# bb_v1.net
KiCad netlist of a schematic drawn in EAGLE
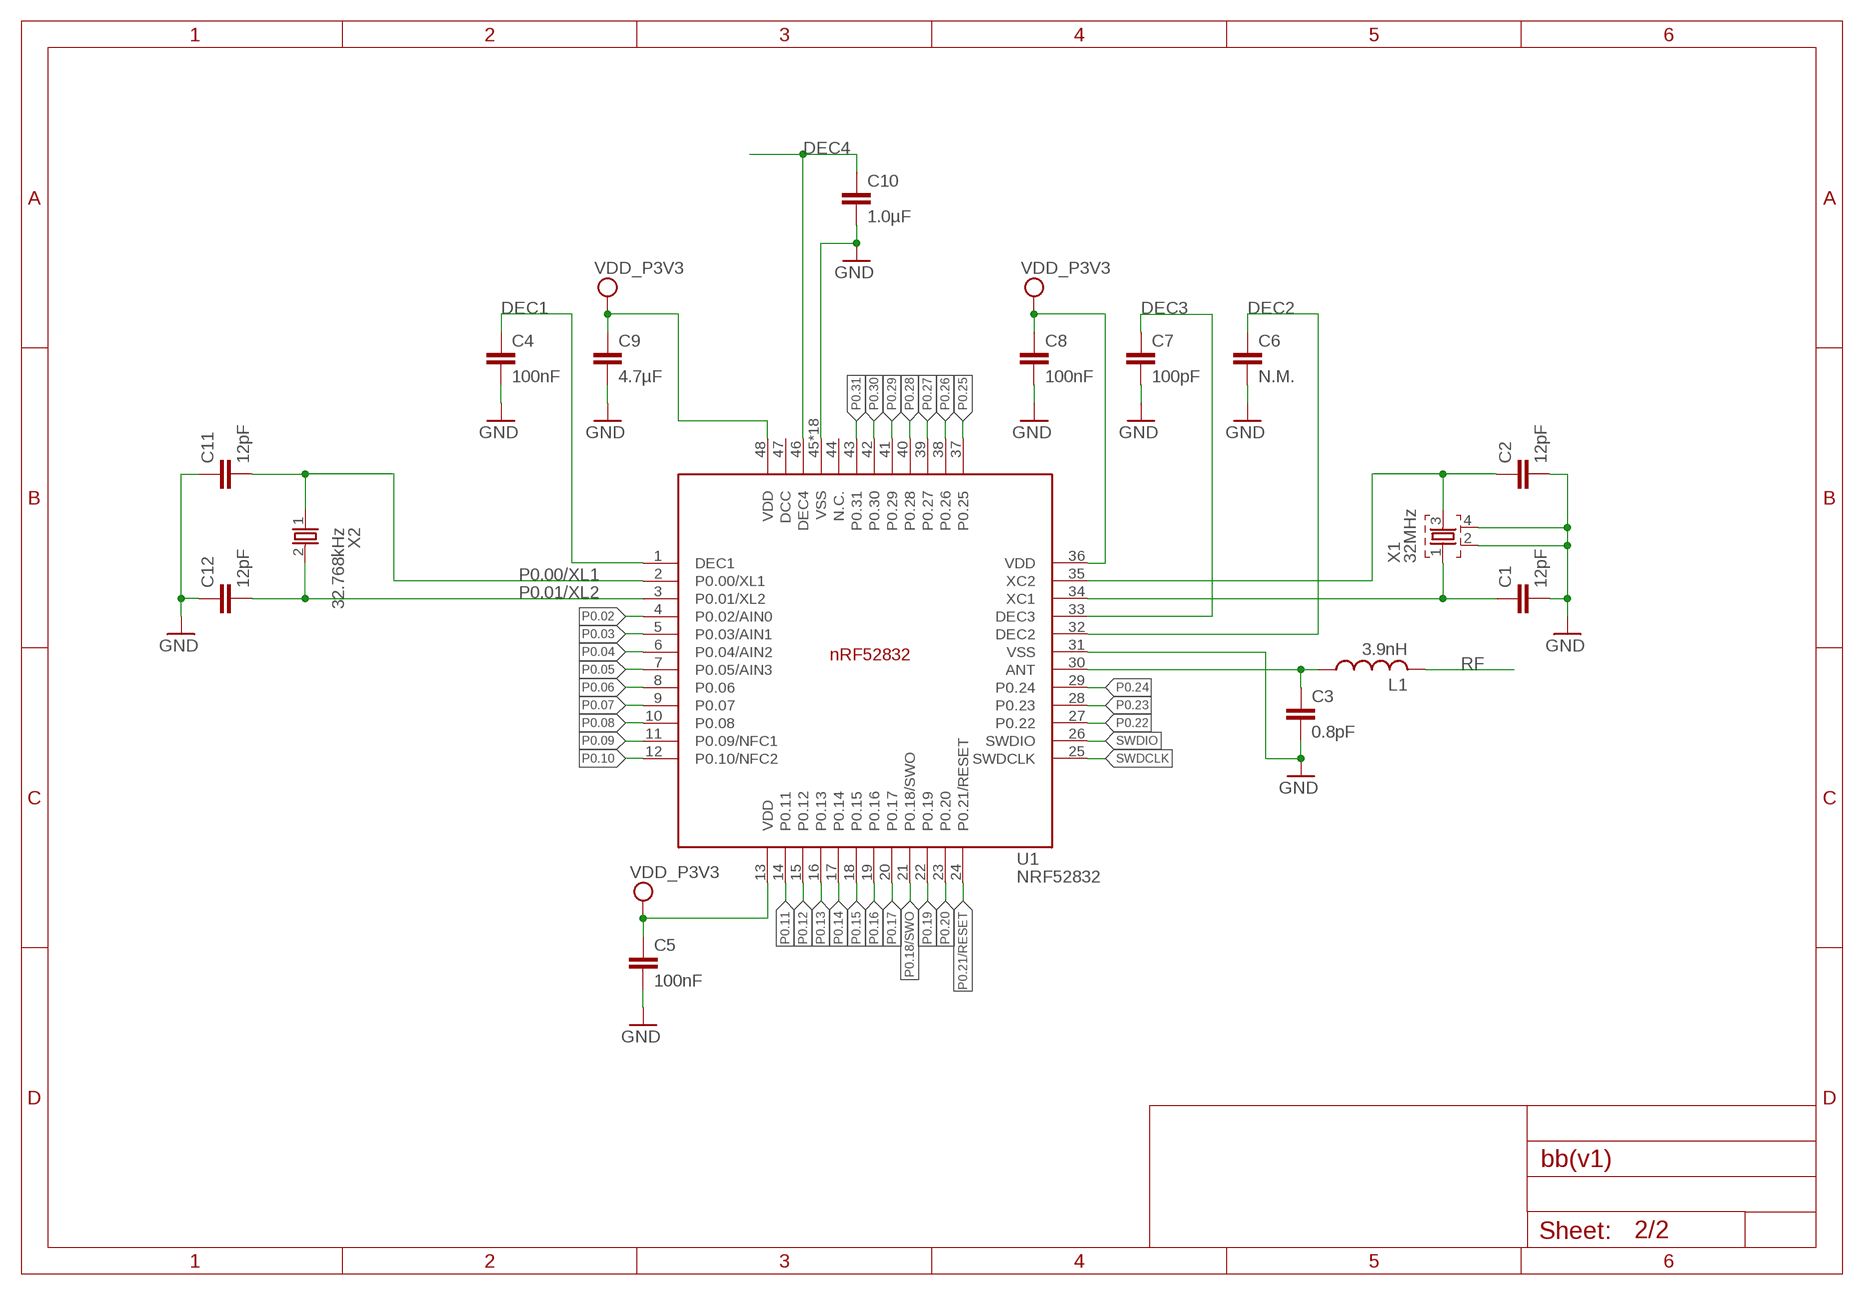
[diagram p0: schematic, sheet 2]

(export (version "E")
  (design (tool "Eeschema 10.0.6"))
  (components
    (comp (ref "C1")
      (value "12pF")
      (footprint "eagle-import:RESC0402_N")
      (libsource (lib "eagle-import") (part "CAPACITOR_0402_N"))
    )
    (comp (ref "C2")
      (value "12pF")
      (footprint "eagle-import:RESC0402_N")
      (libsource (lib "eagle-import") (part "CAPACITOR_0402_N"))
    )
    (comp (ref "C3")
      (value "0.8pF")
      (footprint "eagle-import:RESC0402_N")
      (libsource (lib "eagle-import") (part "CAPACITOR_0402_N"))
    )
    (comp (ref "C4")
      (value "100nF")
      (footprint "eagle-import:RESC0402_N")
      (libsource (lib "eagle-import") (part "CAPACITOR_0402_N"))
    )
    (comp (ref "C5")
      (value "100nF")
      (footprint "eagle-import:RESC0402_N")
      (libsource (lib "eagle-import") (part "CAPACITOR_0402_N"))
    )
    (comp (ref "C6")
      (value "N.M.")
      (footprint "eagle-import:RESC0402_N")
      (libsource (lib "eagle-import") (part "CAPACITOR_0402_N"))
    )
    (comp (ref "C7")
      (value "100pF")
      (footprint "eagle-import:RESC0402_N")
      (libsource (lib "eagle-import") (part "CAPACITOR_0402_N"))
    )
    (comp (ref "C8")
      (value "100nF")
      (footprint "eagle-import:RESC0402_N")
      (libsource (lib "eagle-import") (part "CAPACITOR_0402_N"))
    )
    (comp (ref "C9")
      (value "4.7µF")
      (footprint "eagle-import:RESC0603_N")
      (libsource (lib "eagle-import") (part "CAPACITOR_0603_N"))
    )
    (comp (ref "C10")
      (value "1.0µF")
      (footprint "eagle-import:RESC0603_N")
      (libsource (lib "eagle-import") (part "CAPACITOR_0603_N"))
    )
    (comp (ref "C11")
      (value "12pF")
      (footprint "eagle-import:RESC0402_N")
      (libsource (lib "eagle-import") (part "CAPACITOR_0402_N"))
    )
    (comp (ref "C12")
      (value "12pF")
      (footprint "eagle-import:RESC0402_N")
      (libsource (lib "eagle-import") (part "CAPACITOR_0402_N"))
    )
    (comp (ref "L1")
      (value "3.9nH")
      (footprint "eagle-import:RESC0402_N")
      (libsource (lib "eagle-import") (part "INDUCTOR_0402_N"))
    )
    (comp (ref "U1")
      (value "NRF52832")
      (footprint "eagle-import:QFN40P600X600X90-48_N")
      (libsource (lib "eagle-import") (part "NRF52832"))
    )
    (comp (ref "X1")
      (value "32MHz")
      (footprint "eagle-import:BT-XTAL_2016_N")
      (libsource (lib "eagle-import") (part "XTAL_32MHZ"))
    )
    (comp (ref "X2")
      (value "32.768kHz")
      (footprint "eagle-import:XTAL_3215_N")
      (libsource (lib "eagle-import") (part "XTAL_32KHZ"))
    )
  )
  (nets
    (net (code "1") (name "DEC1") (class "Default")
      (node (ref "C4") (pin "1") (pinfunction "1_1") (pintype "passive"))
      (node (ref "U1") (pin "1") (pinfunction "DEC1_1") (pintype "power_in"))
    )
    (net (code "2") (name "DEC2") (class "Default")
      (node (ref "C6") (pin "1") (pinfunction "1_1") (pintype "passive"))
      (node (ref "U1") (pin "32") (pinfunction "DEC2_32") (pintype "bidirectional"))
    )
    (net (code "3") (name "DEC3") (class "Default")
      (node (ref "C7") (pin "1") (pinfunction "1_1") (pintype "passive"))
      (node (ref "U1") (pin "33") (pinfunction "DEC3_33") (pintype "bidirectional"))
    )
    (net (code "4") (name "DEC4") (class "Default")
      (node (ref "C10") (pin "1") (pinfunction "1_1") (pintype "passive"))
      (node (ref "U1") (pin "46") (pinfunction "DEC4_46") (pintype "power_in"))
    )
    (net (code "5") (name "GND") (class "Default")
      (node (ref "C1") (pin "2") (pinfunction "2_2") (pintype "passive"))
      (node (ref "C10") (pin "2") (pinfunction "2_2") (pintype "passive"))
      (node (ref "C11") (pin "1") (pinfunction "1_1") (pintype "passive"))
      (node (ref "C12") (pin "1") (pinfunction "1_1") (pintype "passive"))
      (node (ref "C2") (pin "2") (pinfunction "2_2") (pintype "passive"))
      (node (ref "C3") (pin "2") (pinfunction "2_2") (pintype "passive"))
      (node (ref "C4") (pin "2") (pinfunction "2_2") (pintype "passive"))
      (node (ref "C5") (pin "2") (pinfunction "2_2") (pintype "passive"))
      (node (ref "C6") (pin "2") (pinfunction "2_2") (pintype "passive"))
      (node (ref "C7") (pin "2") (pinfunction "2_2") (pintype "passive"))
      (node (ref "C8") (pin "2") (pinfunction "2_2") (pintype "passive"))
      (node (ref "C9") (pin "2") (pinfunction "2_2") (pintype "passive"))
      (node (ref "U1") (pin "31") (pinfunction "VSS_31") (pintype "bidirectional"))
      (node (ref "U1") (pin "45") (pinfunction "VSS_45") (pintype "power_in"))
      (node (ref "U1") (pin "PAD") (pinfunction "VSS_PAD") (pintype "power_in"))
      (node (ref "U1") (pin "PAD@VIA01") (pinfunction "VSS_PAD@VIA01") (pintype "power_in"))
      (node (ref "U1") (pin "PAD@VIA02") (pinfunction "VSS_PAD@VIA02") (pintype "power_in"))
      (node (ref "U1") (pin "PAD@VIA03") (pinfunction "VSS_PAD@VIA03") (pintype "power_in"))
      (node (ref "U1") (pin "PAD@VIA04") (pinfunction "VSS_PAD@VIA04") (pintype "power_in"))
      (node (ref "U1") (pin "PAD@VIA05") (pinfunction "VSS_PAD@VIA05") (pintype "power_in"))
      (node (ref "U1") (pin "PAD@VIA06") (pinfunction "VSS_PAD@VIA06") (pintype "power_in"))
      (node (ref "U1") (pin "PAD@VIA07") (pinfunction "VSS_PAD@VIA07") (pintype "power_in"))
      (node (ref "U1") (pin "PAD@VIA08") (pinfunction "VSS_PAD@VIA08") (pintype "power_in"))
      (node (ref "U1") (pin "PAD@VIA09") (pinfunction "VSS_PAD@VIA09") (pintype "power_in"))
      (node (ref "U1") (pin "PAD@VIA10") (pinfunction "VSS_PAD@VIA10") (pintype "power_in"))
      (node (ref "U1") (pin "PAD@VIA11") (pinfunction "VSS_PAD@VIA11") (pintype "power_in"))
      (node (ref "U1") (pin "PAD@VIA12") (pinfunction "VSS_PAD@VIA12") (pintype "power_in"))
      (node (ref "U1") (pin "PAD@VIA13") (pinfunction "VSS_PAD@VIA13") (pintype "power_in"))
      (node (ref "U1") (pin "PAD@VIA14") (pinfunction "VSS_PAD@VIA14") (pintype "power_in"))
      (node (ref "U1") (pin "PAD@VIA15") (pinfunction "VSS_PAD@VIA15") (pintype "power_in"))
      (node (ref "U1") (pin "PAD@VIA16") (pinfunction "VSS_PAD@VIA16") (pintype "power_in"))
      (node (ref "X1") (pin "2") (pinfunction "2_2") (pintype "passive"))
      (node (ref "X1") (pin "4") (pinfunction "4_4") (pintype "passive"))
    )
    (net (code "6") (name "Net-(U1-ANT)") (class "Default")
      (node (ref "C3") (pin "1") (pinfunction "1_1") (pintype "passive"))
      (node (ref "L1") (pin "1") (pinfunction "1_1") (pintype "passive"))
      (node (ref "U1") (pin "30") (pinfunction "ANT_30") (pintype "bidirectional"))
    )
    (net (code "7") (name "Net-(U1-XC1)") (class "Default")
      (node (ref "C1") (pin "1") (pinfunction "1_1") (pintype "passive"))
      (node (ref "U1") (pin "34") (pinfunction "XC1_34") (pintype "input"))
      (node (ref "X1") (pin "1") (pinfunction "1_1") (pintype "passive"))
    )
    (net (code "8") (name "Net-(U1-XC2)") (class "Default")
      (node (ref "C2") (pin "1") (pinfunction "1_1") (pintype "passive"))
      (node (ref "U1") (pin "35") (pinfunction "XC2_35") (pintype "output"))
      (node (ref "X1") (pin "3") (pinfunction "3_3") (pintype "passive"))
    )
    (net (code "9") (name "P0.00{slash}XL1") (class "Default")
      (node (ref "C11") (pin "2") (pinfunction "2_2") (pintype "passive"))
      (node (ref "U1") (pin "2") (pinfunction "P0.00/XL1_2") (pintype "bidirectional"))
      (node (ref "X2") (pin "1") (pinfunction "1_1") (pintype "passive"))
    )
    (net (code "10") (name "P0.01{slash}XL2") (class "Default")
      (node (ref "C12") (pin "2") (pinfunction "2_2") (pintype "passive"))
      (node (ref "U1") (pin "3") (pinfunction "P0.01/XL2_3") (pintype "bidirectional"))
      (node (ref "X2") (pin "2") (pinfunction "2_2") (pintype "passive"))
    )
    (net (code "11") (name "P0.02") (class "Default")
      (node (ref "U1") (pin "4") (pinfunction "P0.02/AIN0_4") (pintype "bidirectional"))
    )
    (net (code "12") (name "P0.03") (class "Default")
      (node (ref "U1") (pin "5") (pinfunction "P0.03/AIN1_5") (pintype "bidirectional"))
    )
    (net (code "13") (name "P0.04") (class "Default")
      (node (ref "U1") (pin "6") (pinfunction "P0.04/AIN2_6") (pintype "bidirectional"))
    )
    (net (code "14") (name "P0.05") (class "Default")
      (node (ref "U1") (pin "7") (pinfunction "P0.05/AIN3_7") (pintype "bidirectional"))
    )
    (net (code "15") (name "P0.06") (class "Default")
      (node (ref "U1") (pin "8") (pinfunction "P0.06_8") (pintype "bidirectional"))
    )
    (net (code "16") (name "P0.07") (class "Default")
      (node (ref "U1") (pin "9") (pinfunction "P0.07_9") (pintype "bidirectional"))
    )
    (net (code "17") (name "P0.08") (class "Default")
      (node (ref "U1") (pin "10") (pinfunction "P0.08_10") (pintype "bidirectional"))
    )
    (net (code "18") (name "P0.09") (class "Default")
      (node (ref "U1") (pin "11") (pinfunction "P0.09/NFC1_11") (pintype "bidirectional"))
    )
    (net (code "19") (name "P0.10") (class "Default")
      (node (ref "U1") (pin "12") (pinfunction "P0.10/NFC2_12") (pintype "bidirectional"))
    )
    (net (code "20") (name "P0.11") (class "Default")
      (node (ref "U1") (pin "14") (pinfunction "P0.11_14") (pintype "bidirectional"))
    )
    (net (code "21") (name "P0.12") (class "Default")
      (node (ref "U1") (pin "15") (pinfunction "P0.12_15") (pintype "bidirectional"))
    )
    (net (code "22") (name "P0.13") (class "Default")
      (node (ref "U1") (pin "16") (pinfunction "P0.13_16") (pintype "bidirectional"))
    )
    (net (code "23") (name "P0.14") (class "Default")
      (node (ref "U1") (pin "17") (pinfunction "P0.14_17") (pintype "bidirectional"))
    )
    (net (code "24") (name "P0.15") (class "Default")
      (node (ref "U1") (pin "18") (pinfunction "P0.15_18") (pintype "bidirectional"))
    )
    (net (code "25") (name "P0.16") (class "Default")
      (node (ref "U1") (pin "19") (pinfunction "P0.16_19") (pintype "bidirectional"))
    )
    (net (code "26") (name "P0.17") (class "Default")
      (node (ref "U1") (pin "20") (pinfunction "P0.17_20") (pintype "bidirectional"))
    )
    (net (code "27") (name "P0.18{slash}SWO") (class "Default")
      (node (ref "U1") (pin "21") (pinfunction "P0.18/SWO_21") (pintype "bidirectional"))
    )
    (net (code "28") (name "P0.19") (class "Default")
      (node (ref "U1") (pin "22") (pinfunction "P0.19_22") (pintype "bidirectional"))
    )
    (net (code "29") (name "P0.20") (class "Default")
      (node (ref "U1") (pin "23") (pinfunction "P0.20_23") (pintype "bidirectional"))
    )
    (net (code "30") (name "P0.21{slash}RESET") (class "Default")
      (node (ref "U1") (pin "24") (pinfunction "P0.21/RESET_24") (pintype "bidirectional"))
    )
    (net (code "31") (name "P0.22") (class "Default")
      (node (ref "U1") (pin "27") (pinfunction "P0.22_27") (pintype "bidirectional"))
    )
    (net (code "32") (name "P0.23") (class "Default")
      (node (ref "U1") (pin "28") (pinfunction "P0.23_28") (pintype "bidirectional"))
    )
    (net (code "33") (name "P0.24") (class "Default")
      (node (ref "U1") (pin "29") (pinfunction "P0.24_29") (pintype "bidirectional"))
    )
    (net (code "34") (name "P0.25") (class "Default")
      (node (ref "U1") (pin "37") (pinfunction "P0.25_37") (pintype "bidirectional"))
    )
    (net (code "35") (name "P0.26") (class "Default")
      (node (ref "U1") (pin "38") (pinfunction "P0.26_38") (pintype "bidirectional"))
    )
    (net (code "36") (name "P0.27") (class "Default")
      (node (ref "U1") (pin "39") (pinfunction "P0.27_39") (pintype "bidirectional"))
    )
    (net (code "37") (name "P0.28") (class "Default")
      (node (ref "U1") (pin "40") (pinfunction "P0.28_40") (pintype "bidirectional"))
    )
    (net (code "38") (name "P0.29") (class "Default")
      (node (ref "U1") (pin "41") (pinfunction "P0.29_41") (pintype "bidirectional"))
    )
    (net (code "39") (name "P0.30") (class "Default")
      (node (ref "U1") (pin "42") (pinfunction "P0.30_42") (pintype "bidirectional"))
    )
    (net (code "40") (name "P0.31") (class "Default")
      (node (ref "U1") (pin "43") (pinfunction "P0.31_43") (pintype "bidirectional"))
    )
    (net (code "41") (name "RF") (class "Default")
      (node (ref "L1") (pin "2") (pinfunction "2_2") (pintype "passive"))
    )
    (net (code "42") (name "SWDCLK") (class "Default")
      (node (ref "U1") (pin "25") (pinfunction "SWDCLK_25") (pintype "input"))
    )
    (net (code "43") (name "SWDIO") (class "Default")
      (node (ref "U1") (pin "26") (pinfunction "SWDIO_26") (pintype "bidirectional"))
    )
    (net (code "44") (name "VDD_P3V3") (class "Default")
      (node (ref "C5") (pin "1") (pinfunction "1_1") (pintype "passive"))
      (node (ref "C8") (pin "1") (pinfunction "1_1") (pintype "passive"))
      (node (ref "C9") (pin "1") (pinfunction "1_1") (pintype "passive"))
      (node (ref "U1") (pin "13") (pinfunction "VDD_13") (pintype "power_in"))
      (node (ref "U1") (pin "36") (pinfunction "VDD_36") (pintype "power_in"))
      (node (ref "U1") (pin "48") (pinfunction "VDD_48") (pintype "power_in"))
    )
    (net (code "45") (name "unconnected-(U1-DCC-Pad47)") (class "Default")
      (node (ref "U1") (pin "47") (pinfunction "DCC_47") (pintype "output"))
    )
    (net (code "46") (name "unconnected-(U1-N.C.-Pad44)") (class "Default")
      (node (ref "U1") (pin "44") (pinfunction "N.C._44") (pintype "no_connect"))
    )
  )
)
